# SCH_plantcare_moisture_module_2025-02-16.net
KiCad netlist of a schematic drawn in EasyEDA
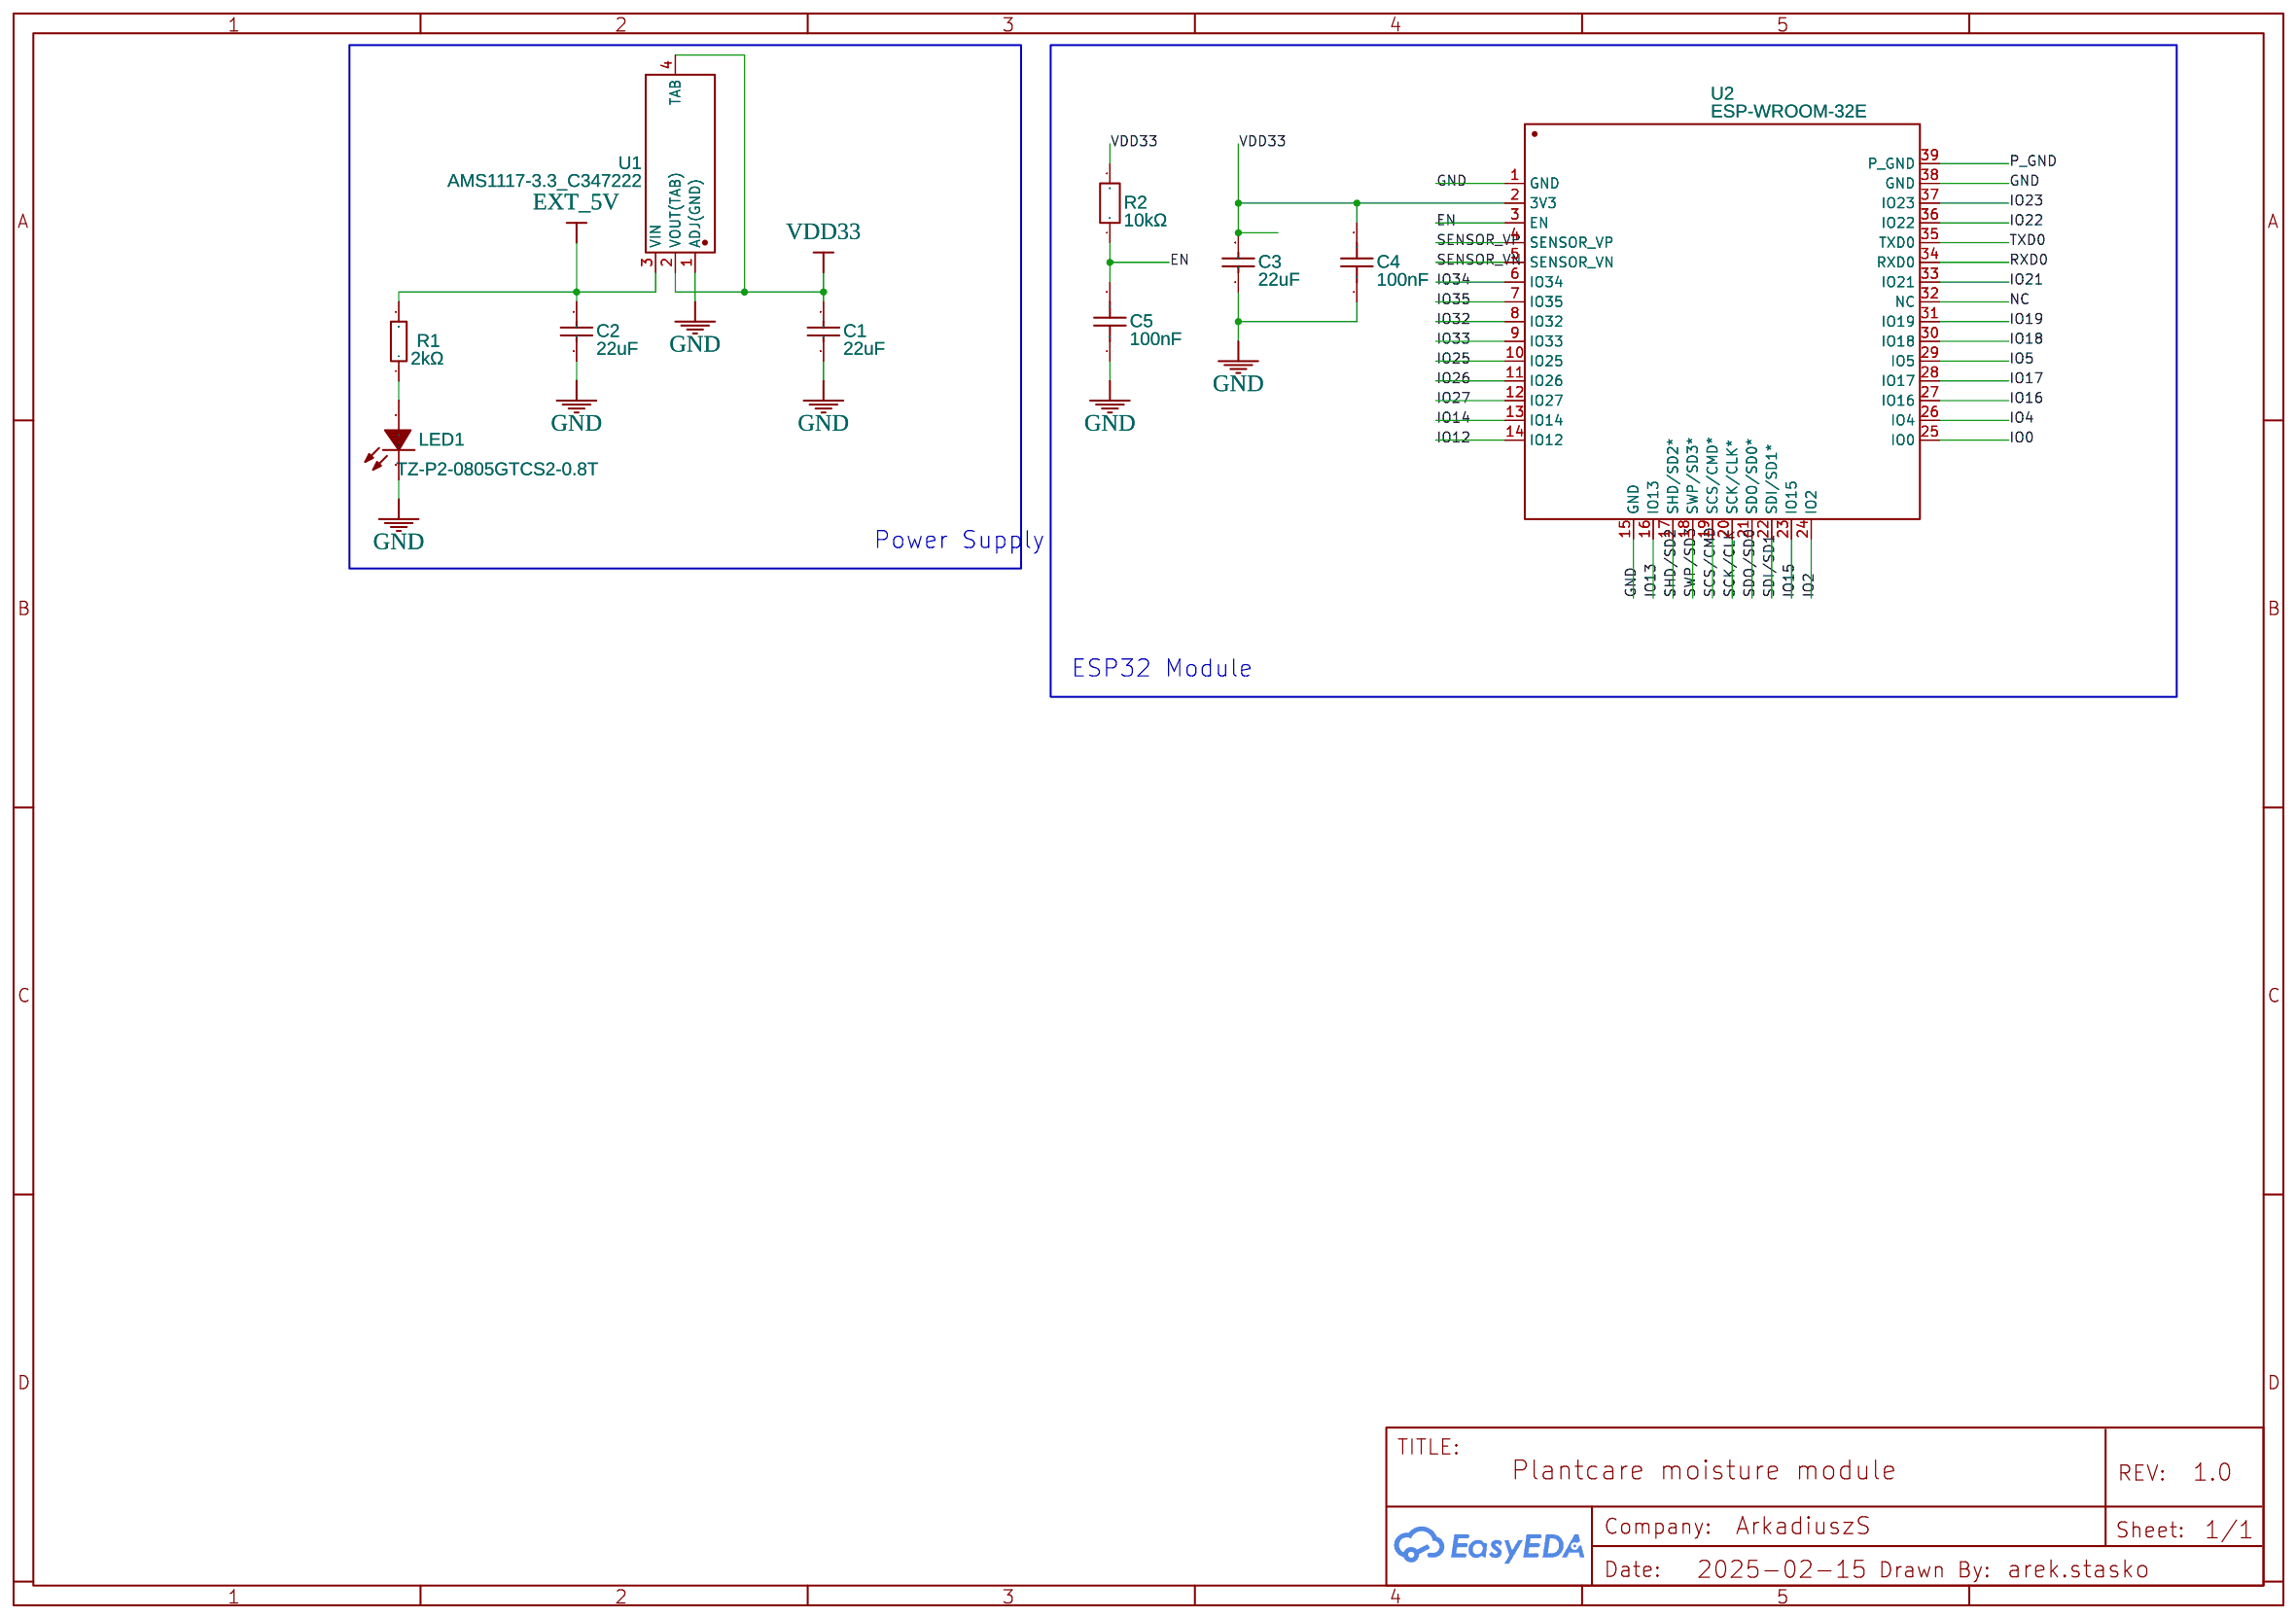
[diagram p0: schematic sheet]

(export (version "E")
  (design (tool "Eeschema 10.0.6"))
  (components
    (comp (ref "C1")
      (value "22uF")
      (fields
        (field (name "Manufacturer Part") "CL21A226MPQNNNE")
        (field (name "Manufacturer") "SAMSUNG(三星)")
      )
      (libsource (lib "") (part "CL21A226MPQNNNE"))
    )
    (comp (ref "C2")
      (value "22uF")
      (fields
        (field (name "Manufacturer Part") "CL21A226MPQNNNE")
        (field (name "Manufacturer") "SAMSUNG(三星)")
      )
      (libsource (lib "") (part "CL21A226MPQNNNE"))
    )
    (comp (ref "C3")
      (value "22uF")
      (fields
        (field (name "Manufacturer Part") "CL21A226MPQNNNE")
        (field (name "Manufacturer") "SAMSUNG(三星)")
      )
      (libsource (lib "") (part "CL21A226MPQNNNE"))
    )
    (comp (ref "C4")
      (value "100nF")
      (fields
        (field (name "Manufacturer Part") "CL10B104KB8NNNC")
        (field (name "Manufacturer") "SAMSUNG(三星)")
      )
      (libsource (lib "") (part "CL10B104KB8NNNC"))
    )
    (comp (ref "C5")
      (value "100nF")
      (fields
        (field (name "Manufacturer Part") "CL10B104KB8NNNC")
        (field (name "Manufacturer") "SAMSUNG(三星)")
      )
      (libsource (lib "") (part "CL10B104KB8NNNC"))
    )
    (comp (ref "LED1")
      (value "TZ-P2-0805GTCS2-0.8T")
      (fields (field (name "Manufacturer") "TUOZHAN(拓展光电)"))
      (libsource (lib "") (part "TZ-P2-0805GTCS2-0.8T"))
    )
    (comp (ref "R1")
      (value "2kΩ")
      (fields
        (field (name "Manufacturer Part") "0603WAF2001T5E")
        (field (name "Manufacturer") "UNI-ROYAL(厚声)")
      )
      (libsource (lib "") (part "0603WAF2001T5E"))
    )
    (comp (ref "R2")
      (value "10kΩ")
      (fields (field (name "Manufacturer Part") "FRC0603J103TS") (field (name "Manufacturer") "FOJAN(富捷)"))
      (libsource (lib "") (part "FRC0603J103TS"))
    )
    (comp (ref "U1")
      (value "AMS1117-3.3_C347222")
      (fields (field (name "Manufacturer Part") "AMS1117-3.3") (field (name "Manufacturer") "UMW(友台半导体)"))
      (libsource (lib "") (part "AMS1117-3.3_C347222"))
    )
    (comp (ref "U2")
      (value "ESP-WROOM-32E")
      (fields (field (name "Manufacturer") "DOIT(四博智联)"))
      (libsource (lib "") (part "ESP-WROOM-32E"))
    )
  )
  (nets
    (net (code "1") (name "/EN") (class "Default")
      (node (ref "C5") (pin "2") (pinfunction "2_2") (pintype "unspecified"))
      (node (ref "R2") (pin "1") (pinfunction "1_1") (pintype "unspecified"))
      (node (ref "U2") (pin "3") (pinfunction "EN_3") (pintype "unspecified"))
    )
    (net (code "2") (name "/IO0") (class "Default")
      (node (ref "U2") (pin "25") (pinfunction "IO0_25") (pintype "unspecified"))
    )
    (net (code "3") (name "/IO2") (class "Default")
      (node (ref "U2") (pin "24") (pinfunction "IO2_24") (pintype "unspecified"))
    )
    (net (code "4") (name "/IO4") (class "Default")
      (node (ref "U2") (pin "26") (pinfunction "IO4_26") (pintype "unspecified"))
    )
    (net (code "5") (name "/IO5") (class "Default")
      (node (ref "U2") (pin "29") (pinfunction "IO5_29") (pintype "unspecified"))
    )
    (net (code "6") (name "/IO12") (class "Default")
      (node (ref "U2") (pin "14") (pinfunction "IO12_14") (pintype "unspecified"))
    )
    (net (code "7") (name "/IO13") (class "Default")
      (node (ref "U2") (pin "16") (pinfunction "IO13_16") (pintype "unspecified"))
    )
    (net (code "8") (name "/IO14") (class "Default")
      (node (ref "U2") (pin "13") (pinfunction "IO14_13") (pintype "unspecified"))
    )
    (net (code "9") (name "/IO15") (class "Default")
      (node (ref "U2") (pin "23") (pinfunction "IO15_23") (pintype "unspecified"))
    )
    (net (code "10") (name "/IO16") (class "Default")
      (node (ref "U2") (pin "27") (pinfunction "IO16_27") (pintype "unspecified"))
    )
    (net (code "11") (name "/IO17") (class "Default")
      (node (ref "U2") (pin "28") (pinfunction "IO17_28") (pintype "unspecified"))
    )
    (net (code "12") (name "/IO18") (class "Default")
      (node (ref "U2") (pin "30") (pinfunction "IO18_30") (pintype "unspecified"))
    )
    (net (code "13") (name "/IO19") (class "Default")
      (node (ref "U2") (pin "31") (pinfunction "IO19_31") (pintype "unspecified"))
    )
    (net (code "14") (name "/IO21") (class "Default")
      (node (ref "U2") (pin "33") (pinfunction "IO21_33") (pintype "unspecified"))
    )
    (net (code "15") (name "/IO22") (class "Default")
      (node (ref "U2") (pin "36") (pinfunction "IO22_36") (pintype "unspecified"))
    )
    (net (code "16") (name "/IO23") (class "Default")
      (node (ref "U2") (pin "37") (pinfunction "IO23_37") (pintype "unspecified"))
    )
    (net (code "17") (name "/IO25") (class "Default")
      (node (ref "U2") (pin "10") (pinfunction "IO25_10") (pintype "unspecified"))
    )
    (net (code "18") (name "/IO26") (class "Default")
      (node (ref "U2") (pin "11") (pinfunction "IO26_11") (pintype "unspecified"))
    )
    (net (code "19") (name "/IO27") (class "Default")
      (node (ref "U2") (pin "12") (pinfunction "IO27_12") (pintype "unspecified"))
    )
    (net (code "20") (name "/IO32") (class "Default")
      (node (ref "U2") (pin "8") (pinfunction "IO32_8") (pintype "unspecified"))
    )
    (net (code "21") (name "/IO33") (class "Default")
      (node (ref "U2") (pin "9") (pinfunction "IO33_9") (pintype "unspecified"))
    )
    (net (code "22") (name "/IO34") (class "Default")
      (node (ref "U2") (pin "6") (pinfunction "IO34_6") (pintype "unspecified"))
    )
    (net (code "23") (name "/IO35") (class "Default")
      (node (ref "U2") (pin "7") (pinfunction "IO35_7") (pintype "unspecified"))
    )
    (net (code "24") (name "/NC") (class "Default")
      (node (ref "U2") (pin "32") (pinfunction "NC_32") (pintype "unspecified"))
    )
    (net (code "25") (name "/P_GND") (class "Default")
      (node (ref "U2") (pin "39") (pinfunction "P_GND_39") (pintype "unspecified"))
    )
    (net (code "26") (name "/RXD0") (class "Default")
      (node (ref "U2") (pin "34") (pinfunction "RXD0_34") (pintype "unspecified"))
    )
    (net (code "27") (name "/SCK{slash}CLK") (class "Default")
      (node (ref "U2") (pin "20") (pinfunction "SCK/CLK*_20") (pintype "unspecified"))
    )
    (net (code "28") (name "/SCS{slash}CMD") (class "Default")
      (node (ref "U2") (pin "19") (pinfunction "SCS/CMD*_19") (pintype "unspecified"))
    )
    (net (code "29") (name "/SDI{slash}SD1") (class "Default")
      (node (ref "U2") (pin "22") (pinfunction "SDI/SD1*_22") (pintype "unspecified"))
    )
    (net (code "30") (name "/SDO{slash}SD0") (class "Default")
      (node (ref "U2") (pin "21") (pinfunction "SDO/SD0*_21") (pintype "unspecified"))
    )
    (net (code "31") (name "/SENSOR_VN") (class "Default")
      (node (ref "U2") (pin "5") (pinfunction "SENSOR_VN_5") (pintype "unspecified"))
    )
    (net (code "32") (name "/SENSOR_VP") (class "Default")
      (node (ref "U2") (pin "4") (pinfunction "SENSOR_VP_4") (pintype "unspecified"))
    )
    (net (code "33") (name "/SHD{slash}SD2") (class "Default")
      (node (ref "U2") (pin "17") (pinfunction "SHD/SD2*_17") (pintype "unspecified"))
    )
    (net (code "34") (name "/SWP{slash}SD3") (class "Default")
      (node (ref "U2") (pin "18") (pinfunction "SWP/SD3*_18") (pintype "unspecified"))
    )
    (net (code "35") (name "/TXD0") (class "Default")
      (node (ref "U2") (pin "35") (pinfunction "TXD0_35") (pintype "unspecified"))
    )
    (net (code "36") (name "EXT_5V") (class "Default")
      (node (ref "C2") (pin "2") (pinfunction "2_2") (pintype "input"))
      (node (ref "R1") (pin "2") (pinfunction "2_2") (pintype "input"))
      (node (ref "U1") (pin "3") (pinfunction "VIN_3") (pintype "unspecified"))
    )
    (net (code "37") (name "GND") (class "Default")
      (node (ref "C1") (pin "1") (pinfunction "1_1") (pintype "input"))
      (node (ref "C2") (pin "1") (pinfunction "1_1") (pintype "input"))
      (node (ref "C3") (pin "1") (pinfunction "1_1") (pintype "input"))
      (node (ref "C4") (pin "1") (pinfunction "1_1") (pintype "unspecified"))
      (node (ref "C5") (pin "1") (pinfunction "1_1") (pintype "unspecified"))
      (node (ref "LED1") (pin "1") (pinfunction "-_1") (pintype "unspecified"))
      (node (ref "U1") (pin "1") (pinfunction "ADJ(GND)_1") (pintype "unspecified"))
      (node (ref "U2") (pin "1") (pinfunction "GND_1") (pintype "unspecified"))
      (node (ref "U2") (pin "15") (pinfunction "GND_15") (pintype "unspecified"))
      (node (ref "U2") (pin "38") (pinfunction "GND_38") (pintype "unspecified"))
    )
    (net (code "38") (name "Net-(LED1-+)") (class "Default")
      (node (ref "LED1") (pin "2") (pinfunction "+_2") (pintype "unspecified"))
      (node (ref "R1") (pin "1") (pinfunction "1_1") (pintype "input"))
    )
    (net (code "39") (name "VDD33") (class "Default")
      (node (ref "C1") (pin "2") (pinfunction "2_2") (pintype "input"))
      (node (ref "C3") (pin "2") (pinfunction "2_2") (pintype "input"))
      (node (ref "C4") (pin "2") (pinfunction "2_2") (pintype "unspecified"))
      (node (ref "R2") (pin "2") (pinfunction "2_2") (pintype "unspecified"))
      (node (ref "U1") (pin "2") (pinfunction "VOUT(TAB)_2") (pintype "unspecified"))
      (node (ref "U1") (pin "4") (pinfunction "TAB_4") (pintype "unspecified"))
      (node (ref "U2") (pin "2") (pinfunction "3V3_2") (pintype "unspecified"))
    )
  )
)
